# DevBOB.net
KiCad netlist of a schematic drawn in Altium Designer
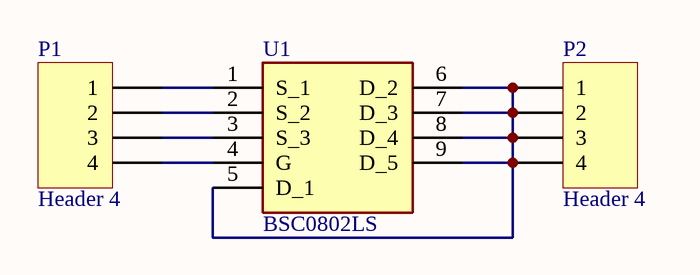
[diagram p0: DevBOB.SchDoc]

(export (version "E")
  (design (tool "Eeschema 10.0.6"))
  (components
    (comp (ref "P1")
      (value "Header 4")
      (footprint "HDR1X4")
      (description "Header, 4-Pin")
      (fields (field (name "PUBLISHER") "Altium Limited"))
      (libsource (lib "Miscellaneous Connectors") (part "Header 4"))
    )
    (comp (ref "P2")
      (value "Header 4")
      (footprint "HDR1X4")
      (description "Header, 4-Pin")
      (fields (field (name "PUBLISHER") "Altium Limited"))
      (libsource (lib "") (part "Header 4_1"))
    )
    (comp (ref "U1")
      (value "BSC0802LS")
      (footprint "TDSON-8")
      (libsource (lib "RcMPPTLib") (part "BSC0802LS"))
    )
  )
  (nets
    (net (code "1") (name "Net-(U1-D_1)") (class "Default")
      (node (ref "P2") (pin "1") (pinfunction "1_1") (pintype "passive"))
      (node (ref "P2") (pin "2") (pinfunction "2_2") (pintype "passive"))
      (node (ref "P2") (pin "3") (pinfunction "3_3") (pintype "passive"))
      (node (ref "P2") (pin "4") (pinfunction "4_4") (pintype "passive"))
      (node (ref "U1") (pin "5") (pinfunction "D_1_5") (pintype "passive"))
      (node (ref "U1") (pin "6") (pinfunction "D_2_6") (pintype "passive"))
      (node (ref "U1") (pin "7") (pinfunction "D_3_7") (pintype "passive"))
      (node (ref "U1") (pin "8") (pinfunction "D_4_8") (pintype "passive"))
      (node (ref "U1") (pin "9") (pinfunction "D_5_9") (pintype "passive"))
    )
    (net (code "2") (name "Net-(U1-G)") (class "Default")
      (node (ref "P1") (pin "4") (pinfunction "4_4") (pintype "passive"))
      (node (ref "U1") (pin "4") (pinfunction "G_4") (pintype "passive"))
    )
    (net (code "3") (name "Net-(U1-S_1)") (class "Default")
      (node (ref "P1") (pin "1") (pinfunction "1_1") (pintype "passive"))
      (node (ref "U1") (pin "1") (pinfunction "S_1_1") (pintype "passive"))
    )
    (net (code "4") (name "Net-(U1-S_2)") (class "Default")
      (node (ref "P1") (pin "2") (pinfunction "2_2") (pintype "passive"))
      (node (ref "U1") (pin "2") (pinfunction "S_2_2") (pintype "passive"))
    )
    (net (code "5") (name "Net-(U1-S_3)") (class "Default")
      (node (ref "P1") (pin "3") (pinfunction "3_3") (pintype "passive"))
      (node (ref "U1") (pin "3") (pinfunction "S_3_3") (pintype "passive"))
    )
  )
)
